# WaterDepth.net
KiCad netlist of a schematic drawn in Altium Designer
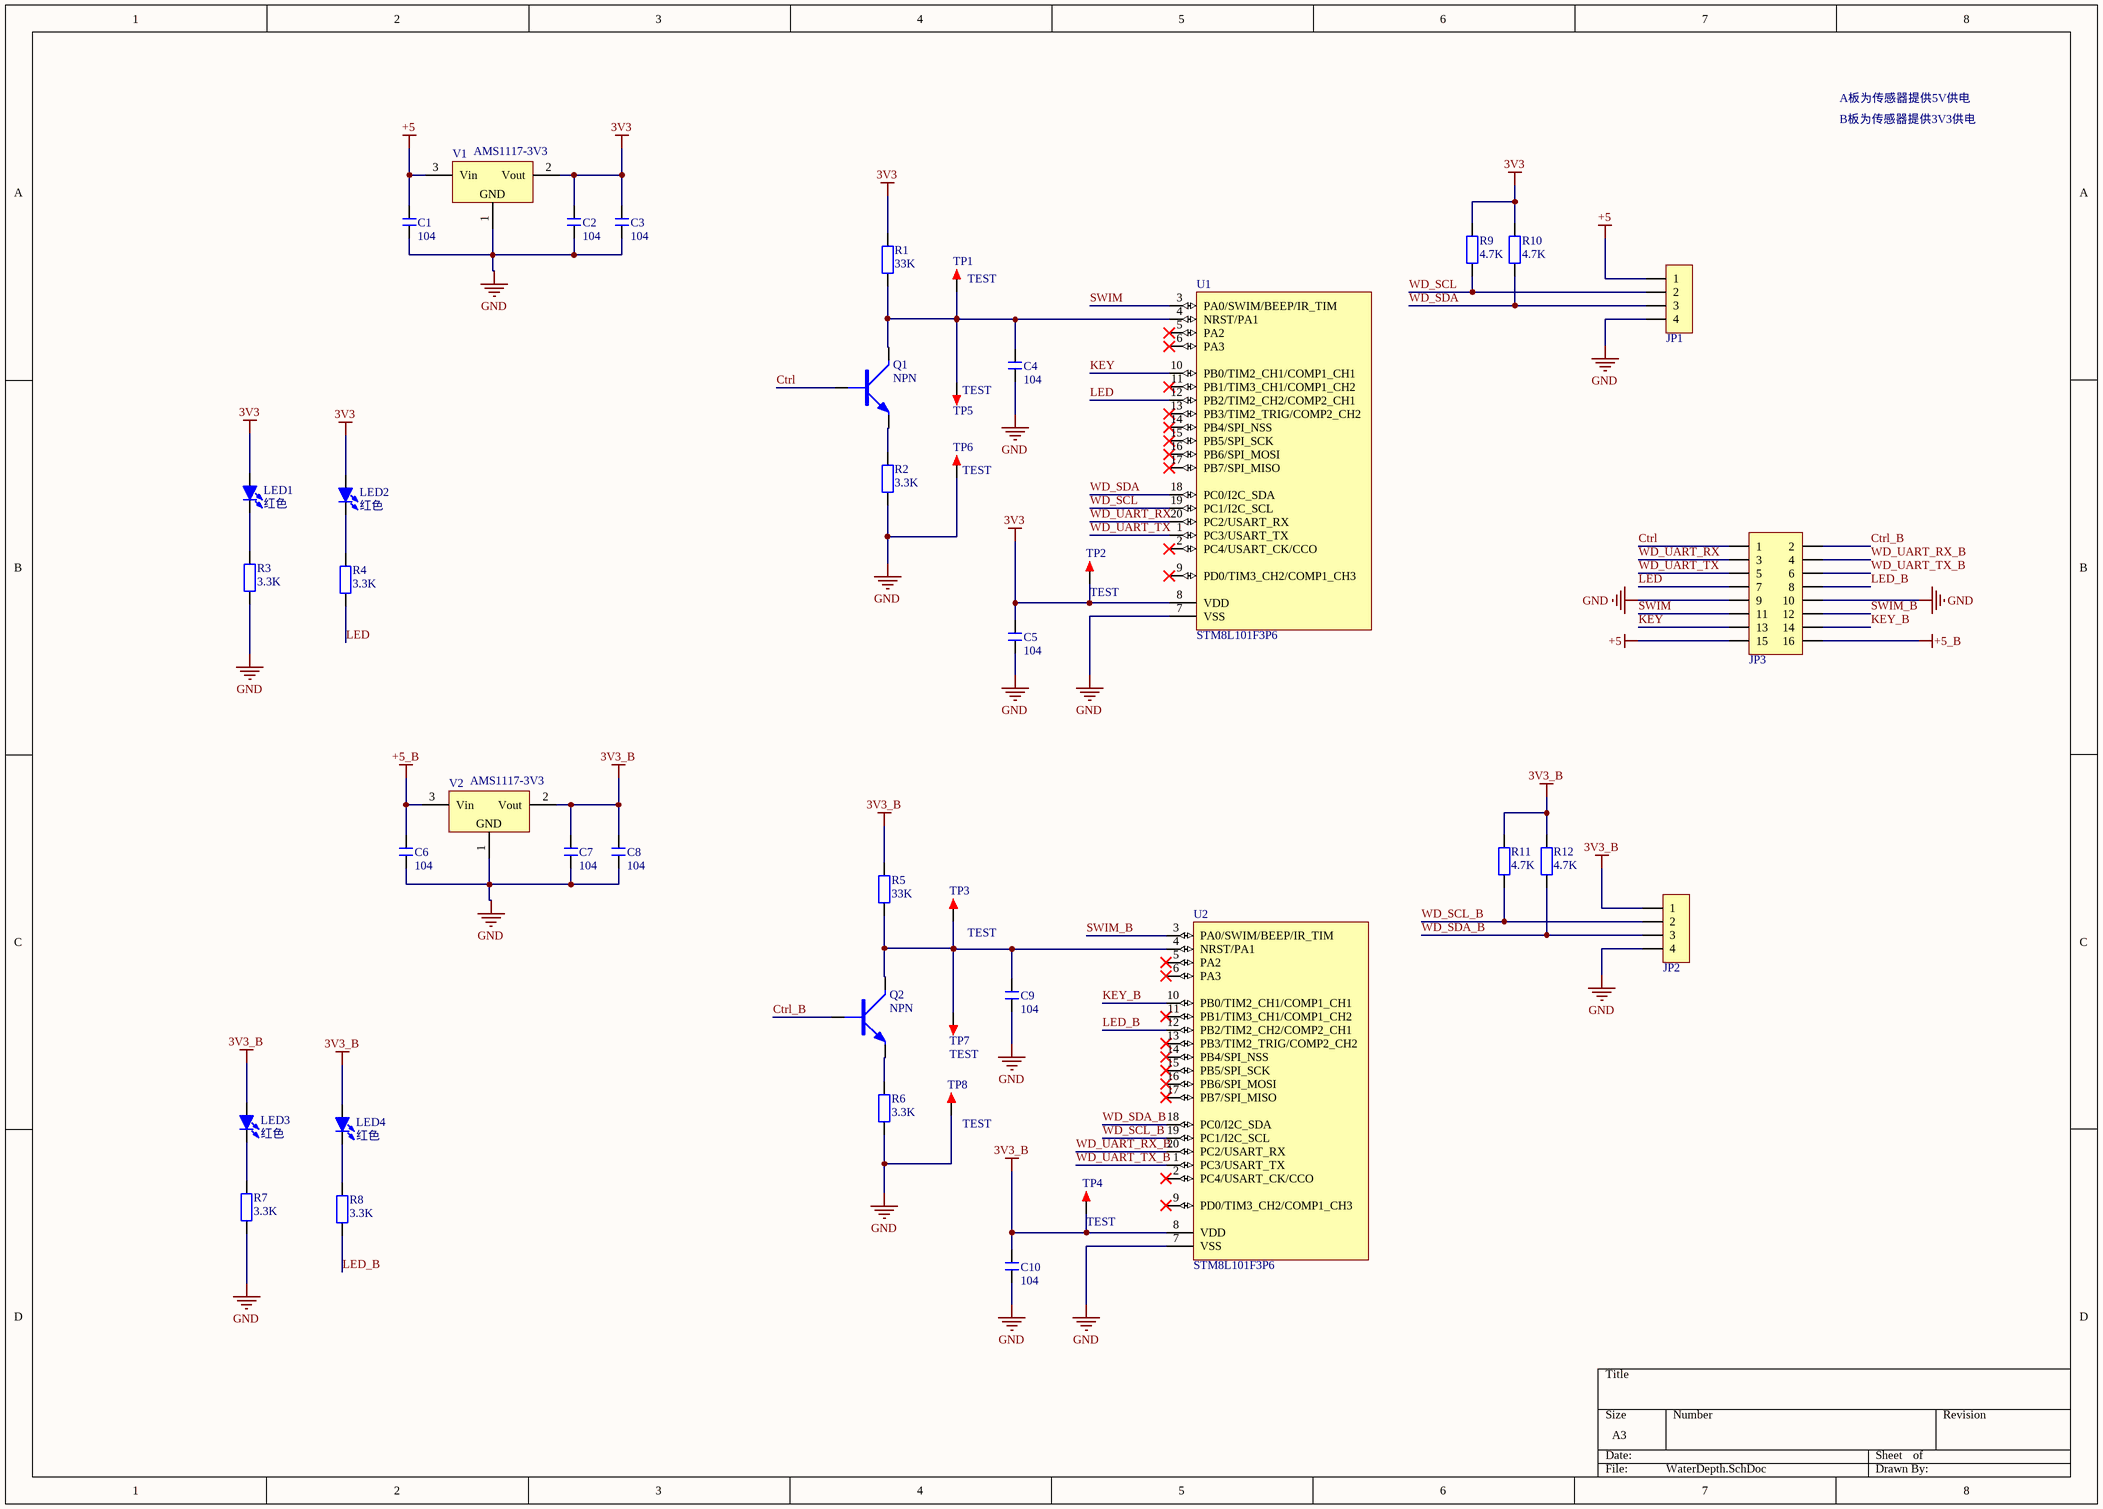
[diagram p0: WaterDepth.SchDoc]

(export (version "E")
  (design (tool "Eeschema 10.0.6"))
  (components
    (comp (ref "C1")
      (value "104")
      (footprint "C 0603_L")
      (description "无极性贴片电容")
      (fields (field (name "版权归属") "源创客"))
      (libsource (lib "3.1   - 电阻-电容-电感") (part "C"))
    )
    (comp (ref "C2")
      (value "104")
      (footprint "C 0603_L")
      (description "无极性贴片电容")
      (fields (field (name "版权归属") "源创客"))
      (libsource (lib "3.1   - 电阻-电容-电感") (part "C"))
    )
    (comp (ref "C3")
      (value "104")
      (footprint "C 0603_L")
      (description "无极性贴片电容")
      (fields (field (name "版权归属") "源创客"))
      (libsource (lib "3.1   - 电阻-电容-电感") (part "C"))
    )
    (comp (ref "C4")
      (value "104")
      (footprint "C 0603_L")
      (description "无极性贴片电容")
      (fields (field (name "版权归属") "源创客"))
      (libsource (lib "3.1   - 电阻-电容-电感") (part "C"))
    )
    (comp (ref "C5")
      (value "104")
      (footprint "C 0603_L")
      (description "无极性贴片电容")
      (fields (field (name "版权归属") "源创客"))
      (libsource (lib "3.1   - 电阻-电容-电感") (part "C"))
    )
    (comp (ref "C6")
      (value "104")
      (footprint "C 0603_L")
      (description "无极性贴片电容")
      (fields (field (name "版权归属") "源创客"))
      (libsource (lib "3.1   - 电阻-电容-电感") (part "C"))
    )
    (comp (ref "C7")
      (value "104")
      (footprint "C 0603_L")
      (description "无极性贴片电容")
      (fields (field (name "版权归属") "源创客"))
      (libsource (lib "3.1   - 电阻-电容-电感") (part "C"))
    )
    (comp (ref "C8")
      (value "104")
      (footprint "C 0603_L")
      (description "无极性贴片电容")
      (fields (field (name "版权归属") "源创客"))
      (libsource (lib "3.1   - 电阻-电容-电感") (part "C"))
    )
    (comp (ref "C9")
      (value "104")
      (footprint "C 0603_L")
      (description "无极性贴片电容")
      (fields (field (name "版权归属") "源创客"))
      (libsource (lib "3.1   - 电阻-电容-电感") (part "C"))
    )
    (comp (ref "C10")
      (value "104")
      (footprint "C 0603_L")
      (description "无极性贴片电容")
      (fields (field (name "版权归属") "源创客"))
      (libsource (lib "3.1   - 电阻-电容-电感") (part "C"))
    )
    (comp (ref "JP1")
      (value "HDR-1X4")
      (footprint "MX 1.25-LS-4P")
      (description "4P接插件")
      (fields (field (name "版权归属") "源创客"))
      (libsource (lib "4.2   - 接插件-脚距1.25") (part "Header 4"))
    )
    (comp (ref "JP2")
      (value "HDR-1X4")
      (footprint "MX 1.25-LS-4P")
      (description "4P接插件")
      (fields (field (name "版权归属") "源创客"))
      (libsource (lib "4.2   - 接插件-脚距1.25") (part "Header 4"))
    )
    (comp (ref "JP3")
      (value "Header 8X2")
      (footprint "HDR2.54-LI-2x8P")
      (description "8*2P接插件")
      (fields (field (name "版权归属") "源创客"))
      (libsource (lib "4.5   - 接插件-脚距2.54") (part "Header 8X2"))
    )
    (comp (ref "LED1")
      (value "红色")
      (footprint "LED 0603W")
      (description "贴片LED")
      (fields (field (name "版权归属") "源创客"))
      (libsource (lib "9.1   - LED") (part "LED-SMD"))
    )
    (comp (ref "LED2")
      (value "红色")
      (footprint "LED 0603W")
      (description "贴片LED")
      (fields (field (name "版权归属") "源创客"))
      (libsource (lib "9.1   - LED") (part "LED-SMD"))
    )
    (comp (ref "LED3")
      (value "红色")
      (footprint "LED 0603W")
      (description "贴片LED")
      (fields (field (name "版权归属") "源创客"))
      (libsource (lib "9.1   - LED") (part "LED-SMD"))
    )
    (comp (ref "LED4")
      (value "红色")
      (footprint "LED 0603W")
      (description "贴片LED")
      (fields (field (name "版权归属") "源创客"))
      (libsource (lib "9.1   - LED") (part "LED-SMD"))
    )
    (comp (ref "Q1")
      (value "NPN")
      (footprint "SOT-23")
      (description "NPN三极管")
      (libsource (lib "三极管") (part "NPN"))
    )
    (comp (ref "Q2")
      (value "NPN")
      (footprint "SOT-23")
      (description "NPN三极管")
      (libsource (lib "三极管") (part "NPN"))
    )
    (comp (ref "R1")
      (value "33K")
      (footprint "R 0603_L")
      (description "贴片电阻")
      (fields (field (name "版权归属") "源创客"))
      (libsource (lib "3.1   - 电阻-电容-电感") (part "R"))
    )
    (comp (ref "R2")
      (value "3.3K")
      (footprint "R 0603_L")
      (description "贴片电阻")
      (fields (field (name "版权归属") "源创客"))
      (libsource (lib "3.1   - 电阻-电容-电感") (part "R"))
    )
    (comp (ref "R3")
      (value "3.3K")
      (footprint "R 0603_L")
      (description "贴片电阻")
      (fields (field (name "版权归属") "源创客"))
      (libsource (lib "3.1   - 电阻-电容-电感") (part "R"))
    )
    (comp (ref "R4")
      (value "3.3K")
      (footprint "R 0603_L")
      (description "贴片电阻")
      (fields (field (name "版权归属") "源创客"))
      (libsource (lib "3.1   - 电阻-电容-电感") (part "R"))
    )
    (comp (ref "R5")
      (value "33K")
      (footprint "R 0603_L")
      (description "贴片电阻")
      (fields (field (name "版权归属") "源创客"))
      (libsource (lib "3.1   - 电阻-电容-电感") (part "R"))
    )
    (comp (ref "R6")
      (value "3.3K")
      (footprint "R 0603_L")
      (description "贴片电阻")
      (fields (field (name "版权归属") "源创客"))
      (libsource (lib "3.1   - 电阻-电容-电感") (part "R"))
    )
    (comp (ref "R7")
      (value "3.3K")
      (footprint "R 0603_L")
      (description "贴片电阻")
      (fields (field (name "版权归属") "源创客"))
      (libsource (lib "3.1   - 电阻-电容-电感") (part "R"))
    )
    (comp (ref "R8")
      (value "3.3K")
      (footprint "R 0603_L")
      (description "贴片电阻")
      (fields (field (name "版权归属") "源创客"))
      (libsource (lib "3.1   - 电阻-电容-电感") (part "R"))
    )
    (comp (ref "R9")
      (value "4.7K")
      (footprint "R 0603_L")
      (description "贴片电阻")
      (fields (field (name "版权归属") "源创客"))
      (libsource (lib "3.1   - 电阻-电容-电感") (part "R"))
    )
    (comp (ref "R10")
      (value "4.7K")
      (footprint "R 0603_L")
      (description "贴片电阻")
      (fields (field (name "版权归属") "源创客"))
      (libsource (lib "3.1   - 电阻-电容-电感") (part "R"))
    )
    (comp (ref "R11")
      (value "4.7K")
      (footprint "R 0603_L")
      (description "贴片电阻")
      (fields (field (name "版权归属") "源创客"))
      (libsource (lib "3.1   - 电阻-电容-电感") (part "R"))
    )
    (comp (ref "R12")
      (value "4.7K")
      (footprint "R 0603_L")
      (description "贴片电阻")
      (fields (field (name "版权归属") "源创客"))
      (libsource (lib "3.1   - 电阻-电容-电感") (part "R"))
    )
    (comp (ref "TP1")
      (value "TEST")
      (footprint "TEST 1")
      (description "测试点")
      (fields (field (name "版权归属") "源创客"))
      (libsource (lib "15.1 - 未分类器件") (part "TEST"))
    )
    (comp (ref "TP2")
      (value "TEST")
      (footprint "TEST 1")
      (description "测试点")
      (fields (field (name "版权归属") "源创客"))
      (libsource (lib "15.1 - 未分类器件") (part "TEST"))
    )
    (comp (ref "TP3")
      (value "TEST")
      (footprint "TEST 1")
      (description "测试点")
      (fields (field (name "版权归属") "源创客"))
      (libsource (lib "15.1 - 未分类器件") (part "TEST"))
    )
    (comp (ref "TP4")
      (value "TEST")
      (footprint "TEST 1")
      (description "测试点")
      (fields (field (name "版权归属") "源创客"))
      (libsource (lib "15.1 - 未分类器件") (part "TEST"))
    )
    (comp (ref "TP5")
      (value "TEST")
      (footprint "TEST 1")
      (description "测试点")
      (fields (field (name "版权归属") "源创客"))
      (libsource (lib "15.1 - 未分类器件") (part "TEST"))
    )
    (comp (ref "TP6")
      (value "TEST")
      (footprint "TEST 1")
      (description "测试点")
      (fields (field (name "版权归属") "源创客"))
      (libsource (lib "15.1 - 未分类器件") (part "TEST"))
    )
    (comp (ref "TP7")
      (value "TEST")
      (footprint "TEST 1")
      (description "测试点")
      (fields (field (name "版权归属") "源创客"))
      (libsource (lib "15.1 - 未分类器件") (part "TEST"))
    )
    (comp (ref "TP8")
      (value "TEST")
      (footprint "TEST 1")
      (description "测试点")
      (fields (field (name "版权归属") "源创客"))
      (libsource (lib "15.1 - 未分类器件") (part "TEST"))
    )
    (comp (ref "U1")
      (value "STM8L101F3P6")
      (footprint "TSSOP-20")
      (description "MCU")
      (libsource (lib "Miscellaneous Devices LC") (part "STM8L101F3P6"))
    )
    (comp (ref "U2")
      (value "STM8L101F3P6")
      (footprint "TSSOP-20")
      (description "MCU")
      (libsource (lib "Miscellaneous Devices LC") (part "STM8L101F3P6"))
    )
    (comp (ref "V1")
      (value "AMS1117-3V3")
      (footprint "SOT89_N")
      (description "三端稳压芯片")
      (fields (field (name "版权归属") "源创客"))
      (libsource (lib "1.3   - 电源类芯片") (part "AMS1117"))
    )
    (comp (ref "V2")
      (value "AMS1117-3V3")
      (footprint "SOT89_N")
      (description "三端稳压芯片")
      (fields (field (name "版权归属") "源创客"))
      (libsource (lib "1.3   - 电源类芯片") (part "AMS1117"))
    )
  )
  (nets
    (net (code "1") (name "+5") (class "Default")
      (node (ref "C1") (pin "2") (pinfunction "2_2") (pintype "passive"))
      (node (ref "JP1") (pin "1") (pinfunction "1_1") (pintype "passive"))
      (node (ref "JP3") (pin "15") (pinfunction "15_15") (pintype "passive"))
      (node (ref "V1") (pin "3") (pinfunction "Vin_3") (pintype "passive"))
    )
    (net (code "2") (name "+5_B") (class "Default")
      (node (ref "C6") (pin "2") (pinfunction "2_2") (pintype "passive"))
      (node (ref "JP3") (pin "16") (pinfunction "16_16") (pintype "passive"))
      (node (ref "V2") (pin "3") (pinfunction "Vin_3") (pintype "passive"))
    )
    (net (code "3") (name "/Ctrl") (class "Default")
      (node (ref "JP3") (pin "1") (pinfunction "1_1") (pintype "passive"))
      (node (ref "Q1") (pin "B") (pinfunction "B_B") (pintype "passive"))
    )
    (net (code "4") (name "/Ctrl_B") (class "Default")
      (node (ref "JP3") (pin "2") (pinfunction "2_2") (pintype "passive"))
      (node (ref "Q2") (pin "B") (pinfunction "B_B") (pintype "passive"))
    )
    (net (code "5") (name "/KEY") (class "Default")
      (node (ref "JP3") (pin "13") (pinfunction "13_13") (pintype "passive"))
      (node (ref "U1") (pin "10") (pinfunction "PB0/TIM2_CH1/COMP1_CH1_10") (pintype "bidirectional"))
    )
    (net (code "6") (name "/KEY_B") (class "Default")
      (node (ref "JP3") (pin "14") (pinfunction "14_14") (pintype "passive"))
      (node (ref "U2") (pin "10") (pinfunction "PB0/TIM2_CH1/COMP1_CH1_10") (pintype "bidirectional"))
    )
    (net (code "7") (name "/LED") (class "Default")
      (node (ref "JP3") (pin "7") (pinfunction "7_7") (pintype "passive"))
      (node (ref "R4") (pin "1") (pinfunction "1_1") (pintype "passive"))
      (node (ref "U1") (pin "12") (pinfunction "PB2/TIM2_CH2/COMP2_CH1_12") (pintype "bidirectional"))
    )
    (net (code "8") (name "/LED_B") (class "Default")
      (node (ref "JP3") (pin "8") (pinfunction "8_8") (pintype "passive"))
      (node (ref "R8") (pin "1") (pinfunction "1_1") (pintype "passive"))
      (node (ref "U2") (pin "12") (pinfunction "PB2/TIM2_CH2/COMP2_CH1_12") (pintype "bidirectional"))
    )
    (net (code "9") (name "/SWIM") (class "Default")
      (node (ref "JP3") (pin "11") (pinfunction "11_11") (pintype "passive"))
      (node (ref "U1") (pin "3") (pinfunction "PA0/SWIM/BEEP/IR_TIM_3") (pintype "bidirectional"))
    )
    (net (code "10") (name "/SWIM_B") (class "Default")
      (node (ref "JP3") (pin "12") (pinfunction "12_12") (pintype "passive"))
      (node (ref "U2") (pin "3") (pinfunction "PA0/SWIM/BEEP/IR_TIM_3") (pintype "bidirectional"))
    )
    (net (code "11") (name "/WD_SCL") (class "Default")
      (node (ref "JP1") (pin "2") (pinfunction "2_2") (pintype "passive"))
      (node (ref "R9") (pin "1") (pinfunction "1_1") (pintype "passive"))
      (node (ref "U1") (pin "19") (pinfunction "PC1/I2C_SCL_19") (pintype "bidirectional"))
    )
    (net (code "12") (name "/WD_SCL_B") (class "Default")
      (node (ref "JP2") (pin "2") (pinfunction "2_2") (pintype "passive"))
      (node (ref "R11") (pin "1") (pinfunction "1_1") (pintype "passive"))
      (node (ref "U2") (pin "19") (pinfunction "PC1/I2C_SCL_19") (pintype "bidirectional"))
    )
    (net (code "13") (name "/WD_SDA") (class "Default")
      (node (ref "JP1") (pin "3") (pinfunction "3_3") (pintype "passive"))
      (node (ref "R10") (pin "1") (pinfunction "1_1") (pintype "passive"))
      (node (ref "U1") (pin "18") (pinfunction "PC0/I2C_SDA_18") (pintype "bidirectional"))
    )
    (net (code "14") (name "/WD_SDA_B") (class "Default")
      (node (ref "JP2") (pin "3") (pinfunction "3_3") (pintype "passive"))
      (node (ref "R12") (pin "1") (pinfunction "1_1") (pintype "passive"))
      (node (ref "U2") (pin "18") (pinfunction "PC0/I2C_SDA_18") (pintype "bidirectional"))
    )
    (net (code "15") (name "/WD_UART_RX") (class "Default")
      (node (ref "JP3") (pin "3") (pinfunction "3_3") (pintype "passive"))
      (node (ref "U1") (pin "20") (pinfunction "PC2/USART_RX_20") (pintype "bidirectional"))
    )
    (net (code "16") (name "/WD_UART_RX_B") (class "Default")
      (node (ref "JP3") (pin "4") (pinfunction "4_4") (pintype "passive"))
      (node (ref "U2") (pin "20") (pinfunction "PC2/USART_RX_20") (pintype "bidirectional"))
    )
    (net (code "17") (name "/WD_UART_TX") (class "Default")
      (node (ref "JP3") (pin "5") (pinfunction "5_5") (pintype "passive"))
      (node (ref "U1") (pin "1") (pinfunction "PC3/USART_TX_1") (pintype "bidirectional"))
    )
    (net (code "18") (name "/WD_UART_TX_B") (class "Default")
      (node (ref "JP3") (pin "6") (pinfunction "6_6") (pintype "passive"))
      (node (ref "U2") (pin "1") (pinfunction "PC3/USART_TX_1") (pintype "bidirectional"))
    )
    (net (code "19") (name "3V3") (class "Default")
      (node (ref "C2") (pin "2") (pinfunction "2_2") (pintype "passive"))
      (node (ref "C3") (pin "2") (pinfunction "2_2") (pintype "passive"))
      (node (ref "C5") (pin "2") (pinfunction "2_2") (pintype "passive"))
      (node (ref "LED1") (pin "1") (pinfunction "A_1") (pintype "passive"))
      (node (ref "LED2") (pin "1") (pinfunction "A_1") (pintype "passive"))
      (node (ref "R1") (pin "2") (pinfunction "2_2") (pintype "passive"))
      (node (ref "R10") (pin "2") (pinfunction "2_2") (pintype "passive"))
      (node (ref "R9") (pin "2") (pinfunction "2_2") (pintype "passive"))
      (node (ref "TP2") (pin "1") (pinfunction "1_1") (pintype "passive"))
      (node (ref "U1") (pin "8") (pinfunction "VDD_8") (pintype "power_in"))
      (node (ref "V1") (pin "2") (pinfunction "Vout_2") (pintype "passive"))
    )
    (net (code "20") (name "3V3_B") (class "Default")
      (node (ref "C10") (pin "2") (pinfunction "2_2") (pintype "passive"))
      (node (ref "C7") (pin "2") (pinfunction "2_2") (pintype "passive"))
      (node (ref "C8") (pin "2") (pinfunction "2_2") (pintype "passive"))
      (node (ref "JP2") (pin "1") (pinfunction "1_1") (pintype "passive"))
      (node (ref "LED3") (pin "1") (pinfunction "A_1") (pintype "passive"))
      (node (ref "LED4") (pin "1") (pinfunction "A_1") (pintype "passive"))
      (node (ref "R11") (pin "2") (pinfunction "2_2") (pintype "passive"))
      (node (ref "R12") (pin "2") (pinfunction "2_2") (pintype "passive"))
      (node (ref "R5") (pin "2") (pinfunction "2_2") (pintype "passive"))
      (node (ref "TP4") (pin "1") (pinfunction "1_1") (pintype "passive"))
      (node (ref "U2") (pin "8") (pinfunction "VDD_8") (pintype "power_in"))
      (node (ref "V2") (pin "2") (pinfunction "Vout_2") (pintype "passive"))
    )
    (net (code "21") (name "GND") (class "Default")
      (node (ref "C1") (pin "1") (pinfunction "1_1") (pintype "passive"))
      (node (ref "C10") (pin "1") (pinfunction "1_1") (pintype "passive"))
      (node (ref "C2") (pin "1") (pinfunction "1_1") (pintype "passive"))
      (node (ref "C3") (pin "1") (pinfunction "1_1") (pintype "passive"))
      (node (ref "C4") (pin "1") (pinfunction "1_1") (pintype "passive"))
      (node (ref "C5") (pin "1") (pinfunction "1_1") (pintype "passive"))
      (node (ref "C6") (pin "1") (pinfunction "1_1") (pintype "passive"))
      (node (ref "C7") (pin "1") (pinfunction "1_1") (pintype "passive"))
      (node (ref "C8") (pin "1") (pinfunction "1_1") (pintype "passive"))
      (node (ref "C9") (pin "1") (pinfunction "1_1") (pintype "passive"))
      (node (ref "JP1") (pin "4") (pinfunction "4_4") (pintype "passive"))
      (node (ref "JP2") (pin "4") (pinfunction "4_4") (pintype "passive"))
      (node (ref "JP3") (pin "10") (pinfunction "10_10") (pintype "passive"))
      (node (ref "JP3") (pin "9") (pinfunction "9_9") (pintype "passive"))
      (node (ref "R2") (pin "1") (pinfunction "1_1") (pintype "passive"))
      (node (ref "R3") (pin "1") (pinfunction "1_1") (pintype "passive"))
      (node (ref "R6") (pin "1") (pinfunction "1_1") (pintype "passive"))
      (node (ref "R7") (pin "1") (pinfunction "1_1") (pintype "passive"))
      (node (ref "TP6") (pin "1") (pinfunction "1_1") (pintype "passive"))
      (node (ref "TP8") (pin "1") (pinfunction "1_1") (pintype "passive"))
      (node (ref "U1") (pin "7") (pinfunction "VSS_7") (pintype "power_in"))
      (node (ref "U2") (pin "7") (pinfunction "VSS_7") (pintype "power_in"))
      (node (ref "V1") (pin "1") (pinfunction "GND_1") (pintype "passive"))
      (node (ref "V2") (pin "1") (pinfunction "GND_1") (pintype "passive"))
    )
    (net (code "22") (name "Net-(LED1-K)") (class "Default")
      (node (ref "LED1") (pin "2") (pinfunction "K_2") (pintype "passive"))
      (node (ref "R3") (pin "2") (pinfunction "2_2") (pintype "passive"))
    )
    (net (code "23") (name "Net-(LED2-K)") (class "Default")
      (node (ref "LED2") (pin "2") (pinfunction "K_2") (pintype "passive"))
      (node (ref "R4") (pin "2") (pinfunction "2_2") (pintype "passive"))
    )
    (net (code "24") (name "Net-(LED3-K)") (class "Default")
      (node (ref "LED3") (pin "2") (pinfunction "K_2") (pintype "passive"))
      (node (ref "R7") (pin "2") (pinfunction "2_2") (pintype "passive"))
    )
    (net (code "25") (name "Net-(LED4-K)") (class "Default")
      (node (ref "LED4") (pin "2") (pinfunction "K_2") (pintype "passive"))
      (node (ref "R8") (pin "2") (pinfunction "2_2") (pintype "passive"))
    )
    (net (code "26") (name "Net-(Q1-PadE)") (class "Default")
      (node (ref "Q1") (pin "E") (pinfunction "E_E") (pintype "passive"))
      (node (ref "R2") (pin "2") (pinfunction "2_2") (pintype "passive"))
    )
    (net (code "27") (name "Net-(Q2-PadE)") (class "Default")
      (node (ref "Q2") (pin "E") (pinfunction "E_E") (pintype "passive"))
      (node (ref "R6") (pin "2") (pinfunction "2_2") (pintype "passive"))
    )
    (net (code "28") (name "Net-(U1-NRST{slash}PA1)") (class "Default")
      (node (ref "C4") (pin "2") (pinfunction "2_2") (pintype "passive"))
      (node (ref "Q1") (pin "C") (pinfunction "C_C") (pintype "passive"))
      (node (ref "R1") (pin "1") (pinfunction "1_1") (pintype "passive"))
      (node (ref "TP1") (pin "1") (pinfunction "1_1") (pintype "passive"))
      (node (ref "TP5") (pin "1") (pinfunction "1_1") (pintype "passive"))
      (node (ref "U1") (pin "4") (pinfunction "NRST/PA1_4") (pintype "bidirectional"))
    )
    (net (code "29") (name "Net-(U2-NRST{slash}PA1)") (class "Default")
      (node (ref "C9") (pin "2") (pinfunction "2_2") (pintype "passive"))
      (node (ref "Q2") (pin "C") (pinfunction "C_C") (pintype "passive"))
      (node (ref "R5") (pin "1") (pinfunction "1_1") (pintype "passive"))
      (node (ref "TP3") (pin "1") (pinfunction "1_1") (pintype "passive"))
      (node (ref "TP7") (pin "1") (pinfunction "1_1") (pintype "passive"))
      (node (ref "U2") (pin "4") (pinfunction "NRST/PA1_4") (pintype "bidirectional"))
    )
    (net (code "30") (name "unconnected-(U1-PA2-Pad5)") (class "Default")
      (node (ref "U1") (pin "5") (pinfunction "PA2_5") (pintype "bidirectional+no_connect"))
    )
    (net (code "31") (name "unconnected-(U1-PA3-Pad6)") (class "Default")
      (node (ref "U1") (pin "6") (pinfunction "PA3_6") (pintype "bidirectional+no_connect"))
    )
    (net (code "32") (name "unconnected-(U1-PB1{slash}TIM3_CH1{slash}COMP1_CH2-Pad11)") (class "Default")
      (node (ref "U1") (pin "11") (pinfunction "PB1/TIM3_CH1/COMP1_CH2_11") (pintype "bidirectional+no_connect"))
    )
    (net (code "33") (name "unconnected-(U1-PB3{slash}TIM2_TRIG{slash}COMP2_CH2-Pad13)") (class "Default")
      (node (ref "U1") (pin "13") (pinfunction "PB3/TIM2_TRIG/COMP2_CH2_13") (pintype "bidirectional+no_connect"))
    )
    (net (code "34") (name "unconnected-(U1-PB4{slash}SPI_NSS-Pad14)") (class "Default")
      (node (ref "U1") (pin "14") (pinfunction "PB4/SPI_NSS_14") (pintype "bidirectional+no_connect"))
    )
    (net (code "35") (name "unconnected-(U1-PB5{slash}SPI_SCK-Pad15)") (class "Default")
      (node (ref "U1") (pin "15") (pinfunction "PB5/SPI_SCK_15") (pintype "bidirectional+no_connect"))
    )
    (net (code "36") (name "unconnected-(U1-PB6{slash}SPI_MOSI-Pad16)") (class "Default")
      (node (ref "U1") (pin "16") (pinfunction "PB6/SPI_MOSI_16") (pintype "bidirectional+no_connect"))
    )
    (net (code "37") (name "unconnected-(U1-PB7{slash}SPI_MISO-Pad17)") (class "Default")
      (node (ref "U1") (pin "17") (pinfunction "PB7/SPI_MISO_17") (pintype "bidirectional+no_connect"))
    )
    (net (code "38") (name "unconnected-(U1-PC4{slash}USART_CK{slash}CCO-Pad2)") (class "Default")
      (node (ref "U1") (pin "2") (pinfunction "PC4/USART_CK/CCO_2") (pintype "bidirectional+no_connect"))
    )
    (net (code "39") (name "unconnected-(U1-PD0{slash}TIM3_CH2{slash}COMP1_CH3-Pad9)") (class "Default")
      (node (ref "U1") (pin "9") (pinfunction "PD0/TIM3_CH2/COMP1_CH3_9") (pintype "bidirectional+no_connect"))
    )
    (net (code "40") (name "unconnected-(U2-PA2-Pad5)") (class "Default")
      (node (ref "U2") (pin "5") (pinfunction "PA2_5") (pintype "bidirectional+no_connect"))
    )
    (net (code "41") (name "unconnected-(U2-PA3-Pad6)") (class "Default")
      (node (ref "U2") (pin "6") (pinfunction "PA3_6") (pintype "bidirectional+no_connect"))
    )
    (net (code "42") (name "unconnected-(U2-PB1{slash}TIM3_CH1{slash}COMP1_CH2-Pad11)") (class "Default")
      (node (ref "U2") (pin "11") (pinfunction "PB1/TIM3_CH1/COMP1_CH2_11") (pintype "bidirectional+no_connect"))
    )
    (net (code "43") (name "unconnected-(U2-PB3{slash}TIM2_TRIG{slash}COMP2_CH2-Pad13)") (class "Default")
      (node (ref "U2") (pin "13") (pinfunction "PB3/TIM2_TRIG/COMP2_CH2_13") (pintype "bidirectional+no_connect"))
    )
    (net (code "44") (name "unconnected-(U2-PB4{slash}SPI_NSS-Pad14)") (class "Default")
      (node (ref "U2") (pin "14") (pinfunction "PB4/SPI_NSS_14") (pintype "bidirectional+no_connect"))
    )
    (net (code "45") (name "unconnected-(U2-PB5{slash}SPI_SCK-Pad15)") (class "Default")
      (node (ref "U2") (pin "15") (pinfunction "PB5/SPI_SCK_15") (pintype "bidirectional+no_connect"))
    )
    (net (code "46") (name "unconnected-(U2-PB6{slash}SPI_MOSI-Pad16)") (class "Default")
      (node (ref "U2") (pin "16") (pinfunction "PB6/SPI_MOSI_16") (pintype "bidirectional+no_connect"))
    )
    (net (code "47") (name "unconnected-(U2-PB7{slash}SPI_MISO-Pad17)") (class "Default")
      (node (ref "U2") (pin "17") (pinfunction "PB7/SPI_MISO_17") (pintype "bidirectional+no_connect"))
    )
    (net (code "48") (name "unconnected-(U2-PC4{slash}USART_CK{slash}CCO-Pad2)") (class "Default")
      (node (ref "U2") (pin "2") (pinfunction "PC4/USART_CK/CCO_2") (pintype "bidirectional+no_connect"))
    )
    (net (code "49") (name "unconnected-(U2-PD0{slash}TIM3_CH2{slash}COMP1_CH3-Pad9)") (class "Default")
      (node (ref "U2") (pin "9") (pinfunction "PD0/TIM3_CH2/COMP1_CH3_9") (pintype "bidirectional+no_connect"))
    )
  )
)
